# JacdacRp2040BrainEc30_124_snapshot_with_.net
KiCad netlist of a schematic drawn in Altium Designer
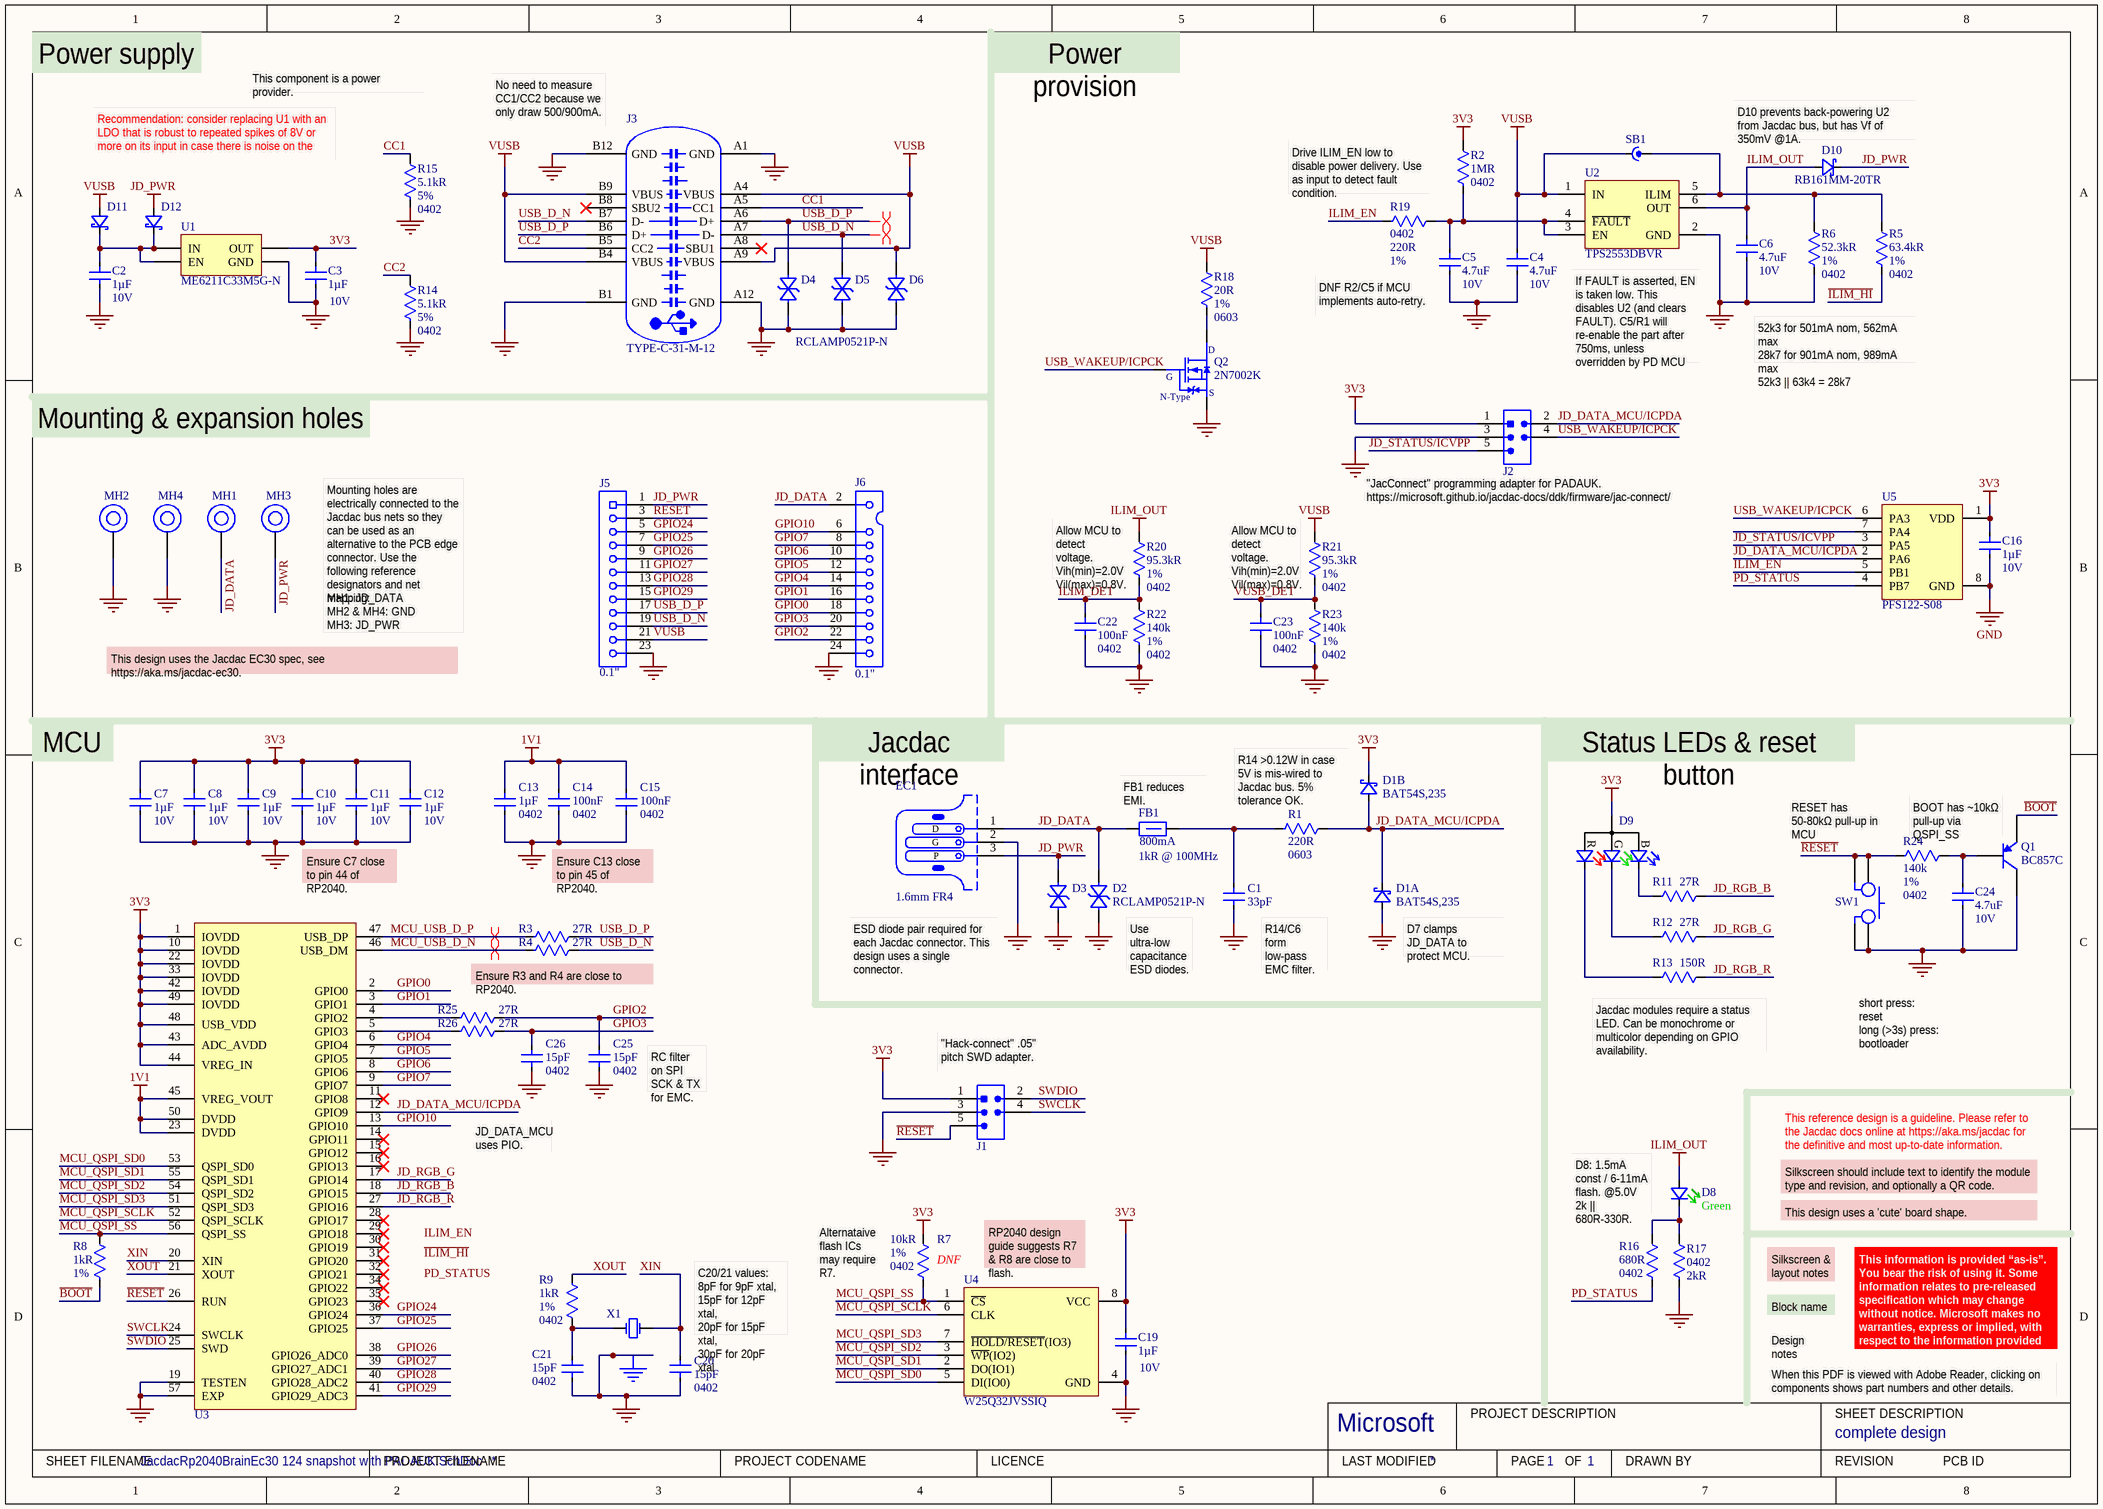
[diagram p0: JacdacRp2040BrainEc30 124 snapshot with PADAUK.SchDoc]

(export (version "E")
  (design (tool "Eeschema 10.0.6"))
  (components
    (comp (ref "C1")
      (value "CL05C330JB51PNC")
      (footprint "C0402_0.55MM - without outline")
      (description "CAP CER 33PF 50V NP0 0402")
      (fields
        (field (name "MANUFACTURER") "Samsung")
        (field (name "TOLERANCE") "5%")
        (field (name "CAPACITANCE") "33pF")
        (field (name "CHECKED") "?")
        (field (name "CREATED") "DG")
      )
      (libsource (lib "Samsung") (part "CL05C330JB51PNC"))
    )
    (comp (ref "C2")
      (value "CL05A105KP5NNNC")
      (footprint "C0402_0.55MM - without outline")
      (description "CAP CER 1UF 10V X5R 0402")
      (fields
        (field (name "MANUFACTURER") "Samsung")
        (field (name "TOLERANCE") "10%")
        (field (name "CAPACITANCE") "1µF")
        (field (name "VOLTAGE RATING") "10V")
        (field (name "CREATED") "DG")
        (field (name "CHECKED") "?")
      )
      (libsource (lib "Samsung") (part "CL05A105KP5NNNC"))
    )
    (comp (ref "C3")
      (value "CL05A105KP5NNNC")
      (footprint "C0402_0.55MM - without outline")
      (description "CAP CER 1UF 10V X5R 0402")
      (fields
        (field (name "MANUFACTURER") "Samsung")
        (field (name "TOLERANCE") "10%")
        (field (name "CAPACITANCE") "1µF")
        (field (name "VOLTAGE RATING") "10V")
        (field (name "CREATED") "DG")
        (field (name "CHECKED") "?")
      )
      (libsource (lib "Samsung") (part "CL05A105KP5NNNC"))
    )
    (comp (ref "C4")
      (value "CL05A475MP5NRNC")
      (footprint "SAMSUNG-CAP-0402:C0402_0.55mm - without outline")
      (description "CAP CER 4.7UF 10V X5R 0402")
      (fields
        (field (name "MANUFACTURER") "Samsung")
        (field (name "TOLERANCE") "20%")
        (field (name "CAPACITANCE") "4.7uF")
        (field (name "VOLTAGE RATING") "10V")
        (field (name "CREATED BY") "D. Gakure")
        (field (name "CHECKED BY") "?")
      )
      (libsource (lib "Samsung") (part "CL05A475MP5NRNC"))
    )
    (comp (ref "C5")
      (value "CL05A475MP5NRNC")
      (footprint "SAMSUNG-CAP-0402:C0402_0.55mm - without outline")
      (description "CAP CER 4.7UF 10V X5R 0402")
      (fields
        (field (name "MANUFACTURER") "Samsung")
        (field (name "TOLERANCE") "20%")
        (field (name "CAPACITANCE") "4.7uF")
        (field (name "VOLTAGE RATING") "10V")
        (field (name "CREATED BY") "D. Gakure")
        (field (name "CHECKED BY") "?")
      )
      (libsource (lib "Samsung") (part "CL05A475MP5NRNC"))
    )
    (comp (ref "C6")
      (value "CL05A475MP5NRNC")
      (footprint "SAMSUNG-CAP-0402:C0402_0.55mm - without outline")
      (description "CAP CER 4.7UF 10V X5R 0402")
      (fields
        (field (name "MANUFACTURER") "Samsung")
        (field (name "TOLERANCE") "20%")
        (field (name "CAPACITANCE") "4.7uF")
        (field (name "VOLTAGE RATING") "10V")
        (field (name "CREATED BY") "D. Gakure")
        (field (name "CHECKED BY") "?")
      )
      (libsource (lib "Samsung") (part "CL05A475MP5NRNC"))
    )
    (comp (ref "C7")
      (value "CL05A105KP5NNNC")
      (footprint "C0402_0.55MM - without outline")
      (description "CAP CER 1UF 10V X5R 0402")
      (fields
        (field (name "MANUFACTURER") "Samsung")
        (field (name "TOLERANCE") "10%")
        (field (name "CAPACITANCE") "1µF")
        (field (name "VOLTAGE RATING") "10V")
        (field (name "CREATED") "DG")
        (field (name "CHECKED") "?")
      )
      (libsource (lib "Samsung") (part "CL05A105KP5NNNC"))
    )
    (comp (ref "C8")
      (value "CL05A105KP5NNNC")
      (footprint "C0402_0.55MM - without outline")
      (description "CAP CER 1UF 10V X5R 0402")
      (fields
        (field (name "MANUFACTURER") "Samsung")
        (field (name "TOLERANCE") "10%")
        (field (name "CAPACITANCE") "1µF")
        (field (name "VOLTAGE RATING") "10V")
        (field (name "CREATED") "DG")
        (field (name "CHECKED") "?")
      )
      (libsource (lib "Samsung") (part "CL05A105KP5NNNC"))
    )
    (comp (ref "C9")
      (value "CL05A105KP5NNNC")
      (footprint "C0402_0.55MM - without outline")
      (description "CAP CER 1UF 10V X5R 0402")
      (fields
        (field (name "MANUFACTURER") "Samsung")
        (field (name "TOLERANCE") "10%")
        (field (name "CAPACITANCE") "1µF")
        (field (name "VOLTAGE RATING") "10V")
        (field (name "CREATED") "DG")
        (field (name "CHECKED") "?")
      )
      (libsource (lib "Samsung") (part "CL05A105KP5NNNC"))
    )
    (comp (ref "C10")
      (value "CL05A105KP5NNNC")
      (footprint "C0402_0.55MM - without outline")
      (description "CAP CER 1UF 10V X5R 0402")
      (fields
        (field (name "MANUFACTURER") "Samsung")
        (field (name "TOLERANCE") "10%")
        (field (name "CAPACITANCE") "1µF")
        (field (name "VOLTAGE RATING") "10V")
        (field (name "CREATED") "DG")
        (field (name "CHECKED") "?")
      )
      (libsource (lib "Samsung") (part "CL05A105KP5NNNC"))
    )
    (comp (ref "C11")
      (value "CL05A105KP5NNNC")
      (footprint "C0402_0.55MM - without outline")
      (description "CAP CER 1UF 10V X5R 0402")
      (fields
        (field (name "MANUFACTURER") "Samsung")
        (field (name "TOLERANCE") "10%")
        (field (name "CAPACITANCE") "1µF")
        (field (name "VOLTAGE RATING") "10V")
        (field (name "CREATED") "DG")
        (field (name "CHECKED") "?")
      )
      (libsource (lib "Samsung") (part "CL05A105KP5NNNC"))
    )
    (comp (ref "C12")
      (value "CL05A105KP5NNNC")
      (footprint "C0402_0.55MM - without outline")
      (description "CAP CER 1UF 10V X5R 0402")
      (fields
        (field (name "MANUFACTURER") "Samsung")
        (field (name "TOLERANCE") "10%")
        (field (name "CAPACITANCE") "1µF")
        (field (name "VOLTAGE RATING") "10V")
        (field (name "CREATED") "DG")
        (field (name "CHECKED") "?")
      )
      (libsource (lib "Samsung") (part "CL05A105KP5NNNC"))
    )
    (comp (ref "C13")
      (value "CL05A105KP5NNNC")
      (footprint "C0402_0.55MM - without outline")
      (description "CAP CER 1UF 10V X5R 0402")
      (fields
        (field (name "MANUFACTURER") "Samsung")
        (field (name "CASE/PACKAGE") "0402")
        (field (name "TOLERANCE") "10%")
        (field (name "CAPACITANCE") "1µF")
        (field (name "CREATED") "DG")
        (field (name "CHECKED") "?")
      )
      (libsource (lib "Samsung") (part "CL05A105KP5NNNC"))
    )
    (comp (ref "C14")
      (value "CL05B104KP5NNNC")
      (footprint "SAMSUNG-CAP-0402:C0402_0.55MM - without outline")
      (description "CAP CER 0.1UF 10V X7R 0402")
      (fields
        (field (name "MANUFACTURER") "Samsung")
        (field (name "TOLERANCE") "10%")
        (field (name "CAPACITANCE") "100nF")
        (field (name "CASE CODE (IMPERIAL)") "0402")
        (field (name "CREATED") "DG")
        (field (name "CHECKED") "?")
      )
      (libsource (lib "Samsung") (part "CL05B104KP5NNNC"))
    )
    (comp (ref "C15")
      (value "CL05B104KP5NNNC")
      (footprint "SAMSUNG-CAP-0402:C0402_0.55MM - without outline")
      (description "CAP CER 0.1UF 10V X7R 0402")
      (fields
        (field (name "MANUFACTURER") "Samsung")
        (field (name "TOLERANCE") "10%")
        (field (name "CAPACITANCE") "100nF")
        (field (name "CASE CODE (IMPERIAL)") "0402")
        (field (name "CREATED") "DG")
        (field (name "CHECKED") "?")
      )
      (libsource (lib "Samsung") (part "CL05B104KP5NNNC"))
    )
    (comp (ref "C16")
      (value "CL05A105KP5NNNC")
      (footprint "SAMSUNG-CAP-0402:C0402_0.55MM - without outline")
      (description "CAP CER 1UF 10V X5R 0402")
      (fields
        (field (name "MANUFACTURER") "Samsung")
        (field (name "TOLERANCE") "10%")
        (field (name "CAPACITANCE") "1µF")
        (field (name "VOLTAGE RATING") "10V")
        (field (name "CREATED") "DG")
        (field (name "CHECKED") "?")
      )
      (libsource (lib "Samsung") (part "CL05A105KP5NNNC"))
    )
    (comp (ref "C19")
      (value "CL05A105KP5NNNC")
      (footprint "C0402_0.55MM - without outline")
      (description "CAP CER 1UF 10V X5R 0402")
      (fields
        (field (name "MANUFACTURER") "Samsung")
        (field (name "TOLERANCE") "10%")
        (field (name "CAPACITANCE") "1µF")
        (field (name "VOLTAGE RATING") "10V")
        (field (name "CREATED") "DG")
        (field (name "CHECKED") "?")
      )
      (libsource (lib "Samsung") (part "CL05A105KP5NNNC"))
    )
    (comp (ref "C20")
      (value "CL05C150JB5NNNC")
      (footprint "C0402_0.55MM - without outline")
      (description "CAP CER 15PF 50V C0G/NP0 0402")
      (fields
        (field (name "MANUFACTURER") "Samsung")
        (field (name "TOLERANCE") "5%")
        (field (name "CAPACITANCE") "15pF")
        (field (name "CASE/PACKAGE") "0402")
      )
      (libsource (lib "Samsung") (part "CL05C150JB5NNNC"))
    )
    (comp (ref "C21")
      (value "CL05C150JB5NNNC")
      (footprint "C0402_0.55MM - without outline")
      (description "CAP CER 15PF 50V C0G/NP0 0402")
      (fields
        (field (name "MANUFACTURER") "Samsung")
        (field (name "TOLERANCE") "5%")
        (field (name "CAPACITANCE") "15pF")
        (field (name "CASE/PACKAGE") "0402")
      )
      (libsource (lib "Samsung") (part "CL05C150JB5NNNC"))
    )
    (comp (ref "C22")
      (value "CL05B104KP5NNNC")
      (footprint "SAMSUNG-CAP-0402:C0402_0.55MM - without outline")
      (description "CAP CER 0.1UF 10V X7R 0402")
      (fields
        (field (name "MANUFACTURER") "Samsung")
        (field (name "TOLERANCE") "10%")
        (field (name "CAPACITANCE") "100nF")
        (field (name "CASE CODE (IMPERIAL)") "0402")
        (field (name "CREATED") "DG")
        (field (name "CHECKED") "?")
      )
      (libsource (lib "Samsung") (part "CL05B104KP5NNNC"))
    )
    (comp (ref "C23")
      (value "CL05B104KP5NNNC")
      (footprint "SAMSUNG-CAP-0402:C0402_0.55MM - without outline")
      (description "CAP CER 0.1UF 10V X7R 0402")
      (fields
        (field (name "MANUFACTURER") "Samsung")
        (field (name "TOLERANCE") "10%")
        (field (name "CAPACITANCE") "100nF")
        (field (name "CASE CODE (IMPERIAL)") "0402")
        (field (name "CREATED") "DG")
        (field (name "CHECKED") "?")
      )
      (libsource (lib "Samsung") (part "CL05B104KP5NNNC"))
    )
    (comp (ref "C24")
      (value "CL05A475MP5NRNC")
      (footprint "SAMSUNG-CAP-0402:C0402_0.55mm - without outline")
      (description "CAP CER 4.7UF 10V X5R 0402")
      (fields
        (field (name "MANUFACTURER") "Samsung")
        (field (name "TOLERANCE") "20%")
        (field (name "CAPACITANCE") "4.7uF")
        (field (name "VOLTAGE RATING") "10V")
        (field (name "CREATED BY") "D. Gakure")
        (field (name "CHECKED BY") "?")
      )
      (libsource (lib "Samsung") (part "CL05A475MP5NRNC"))
    )
    (comp (ref "C25")
      (value "CL05C150JB5NNNC")
      (footprint "SAMSUNG-CAP-0402:C0402_0.55MM - without outline")
      (description "CAP CER 15PF 50V C0G/NP0 0402")
      (fields
        (field (name "MANUFACTURER") "Samsung")
        (field (name "TOLERANCE") "5%")
        (field (name "CAPACITANCE") "15pF")
        (field (name "CASE/PACKAGE") "0402")
      )
      (libsource (lib "Samsung") (part "CL05C150JB5NNNC"))
    )
    (comp (ref "C26")
      (value "CL05C150JB5NNNC")
      (footprint "SAMSUNG-CAP-0402:C0402_0.55MM - without outline")
      (description "CAP CER 15PF 50V C0G/NP0 0402")
      (fields
        (field (name "MANUFACTURER") "Samsung")
        (field (name "TOLERANCE") "5%")
        (field (name "CAPACITANCE") "15pF")
        (field (name "CASE/PACKAGE") "0402")
      )
      (libsource (lib "Samsung") (part "CL05C150JB5NNNC"))
    )
    (comp (ref "D1")
      (value "BAT54S")
      (footprint "NXP-BAT54S-TO-236AB - without outline")
      (description "DIODE ARRAY SCHOTTKY 30V SOT23")
      (fields (field (name "MANUFACTURER") "Nexperia") (field (name "MANUFACTURER PART NUMBER") "BAT54S,235"))
      (libsource (lib "NXP") (part "BAT54S"))
    )
    (comp (ref "D2")
      (value "RCLAMP0521P-N")
      (footprint "TVS 0402 - L")
      (description "Bidirectional 5V (Max) 6V 16V 3.5A (8/20us) 0402 TVS RoHS")
      (fields
        (field (name "MANUFACTURER") "Born Semiconductor")
        (field (name "MANUFACTURER PART NUMBER") "RCLAMP0521P-N")
        (field (name "CREATED BY") "D Gakure")
        (field (name "CHECKED BY") "?")
      )
      (libsource (lib "BornSemiconductor") (part "RCLAMP0521P-N"))
    )
    (comp (ref "D3")
      (value "RCLAMP0521P-N")
      (footprint "TVS 0402 - L")
      (description "Bidirectional 5V (Max) 6V 16V 3.5A (8/20us) 0402 TVS RoHS")
      (fields
        (field (name "MANUFACTURER") "Born Semiconductor")
        (field (name "CREATED BY") "D Gakure")
        (field (name "CHECKED BY") "?")
      )
      (libsource (lib "BornSemiconductor") (part "RCLAMP0521P-N"))
    )
    (comp (ref "D4")
      (value "RCLAMP0521P-N")
      (footprint "TVS 0402 - L")
      (description "Bidirectional 5V (Max) 6V 16V 3.5A (8/20us) 0402 TVS RoHS")
      (fields
        (field (name "MANUFACTURER") "Born Semiconductor")
        (field (name "CREATED BY") "D Gakure")
        (field (name "CHECKED BY") "?")
      )
      (libsource (lib "BornSemiconductor") (part "RCLAMP0521P-N"))
    )
    (comp (ref "D5")
      (value "RCLAMP0521P-N")
      (footprint "TVS 0402 - L")
      (description "Bidirectional 5V (Max) 6V 16V 3.5A (8/20us) 0402 TVS RoHS")
      (fields
        (field (name "MANUFACTURER") "Born Semiconductor")
        (field (name "CREATED BY") "D Gakure")
        (field (name "CHECKED BY") "?")
      )
      (libsource (lib "BornSemiconductor") (part "RCLAMP0521P-N"))
    )
    (comp (ref "D6")
      (value "RCLAMP0521P-N")
      (footprint "TVS 0402 - L")
      (description "Bidirectional 5V (Max) 6V 16V 3.5A (8/20us) 0402 TVS RoHS")
      (fields
        (field (name "MANUFACTURER") "Born Semiconductor")
        (field (name "MANUFACTURER PART NUMBER") "RCLAMP0521P-N")
        (field (name "CREATED BY") "D Gakure")
        (field (name "CHECKED BY") "?")
      )
      (libsource (lib "BornSemiconductor") (part "RCLAMP0521P-N"))
    )
    (comp (ref "D8")
      (value "~")
      (footprint "Green_0603:0603 Green")
      (description "LED GREEN DIFFUSED 0603 SMD")
      (fields
        (field (name "MANUFACTURER") "Everlight Elec")
        (field (name "MANUFACTURER PART NUMBER") "19-217/GHC-YR1S2/3T")
        (field (name "COLOUR") "Green")
      )
      (libsource (lib "EverlightElec") (part "19-217/GHC-YR1S2/3T"))
    )
    (comp (ref "D9")
      (value "TZ-P4-1615RGBTCA1-0.55T")
      (footprint "TZ-P4-1615RGBTCA1-0.55T")
      (description "1615 Light Emitting Diodes (LED) RoHS")
      (fields
        (field (name "MANUFACTURER") "TUOZHAN")
        (field (name "CREATED BY") "D. Gakure")
        (field (name "CHECKED BY") "?")
      )
      (libsource (lib "Tuozhan") (part "TZ-P4-1615RGBTCA1-0.55T"))
    )
    (comp (ref "D10")
      (value "RB161MM-20TR")
      (footprint "SOD-123F:SOD-123F - without outline")
      (description "ROHM - RB161MM-20TR - Schottky-Gleichrichterdiode, 20 V, 1 A, Einfach, SOD-123FL, 2 Pin(s), 350 mV")
      (fields (field (name "MANUFACTURER") "Rohm") (field (name "MANUFACTURER PART NUMBER") "RB161MM-20TR"))
      (libsource (lib "Rohm") (part "RB161MM-20TR"))
    )
    (comp (ref "D11")
      (value "RB161MM-20TR")
      (footprint "SOD-123F:SOD-123F - without outline")
      (description "ROHM - RB161MM-20TR - Schottky-Gleichrichterdiode, 20 V, 1 A, Einfach, SOD-123FL, 2 Pin(s), 350 mV")
      (fields (field (name "MANUFACTURER") "Rohm"))
      (libsource (lib "Rohm") (part "RB161MM-20TR"))
    )
    (comp (ref "D12")
      (value "RB161MM-20TR")
      (footprint "SOD-123F:SOD-123F - without outline")
      (description "ROHM - RB161MM-20TR - Schottky-Gleichrichterdiode, 20 V, 1 A, Einfach, SOD-123FL, 2 Pin(s), 350 mV")
      (fields (field (name "MANUFACTURER") "Rohm"))
      (libsource (lib "Rohm") (part "RB161MM-20TR"))
    )
    (comp (ref "EC1")
      (value "3 pin JACDAC edge connector")
      (footprint "JACDAC_edge_connector:JACDAC_EDGE_CONNECTOR_NO_TRACES")
      (description "3 pin Jacdac edge connector 1.27mm pitch")
      (fields
        (field (name "MANUFACTURER PART NUMBER") "JACDAC_EDGE_CONNECTOR")
        (field (name "PCB TYPE") "1.6mm FR4")
        (field (name "CHECKED BY") "?")
        (field (name "CREATED BY") "D. Gakure")
      )
      (libsource (lib "generic-con") (part "Jacdac edge connector"))
    )
    (comp (ref "FB1")
      (value "TDK MPZ1608S102ATA00")
      (footprint "TDK MPZ1608 0.8mm - without outline")
      (description "0603 1k@100MHz 0.8A chip")
      (fields
        (field (name "TOLERANCE") "25%")
        (field (name "MANUFACTURER") "TDK")
        (field (name "CURRENT RATING") "800mA")
        (field (name "IMPEDANCE") "1kR @ 100MHz")
      )
      (libsource (lib "TDK") (part "TDK MPZ1608S102ATA00"))
    )
    (comp (ref "J1")
      (value "Hack Connect Mini 1.27 mm pitch 2-row")
      (footprint "HACK_CONNECT_MINI_5_X_1_27")
      (libsource (lib "generic-con") (part "HACK_CONNECT_MINI"))
    )
    (comp (ref "J2")
      (value "Hack Connect Mini 1.27 mm pitch 2-row")
      (footprint "HackConnect:HACK_CONNECT_MINI_5_X_1_27_0.559mm_TH")
      (libsource (lib "generic-con") (part "HACK_CONNECT_MINI"))
    )
    (comp (ref "J3")
      (value "TYPE-C-31-M-12")
      (footprint "TYPE-C-31-M-12")
      (description "USB - Type C Female 16 USB Connectors RoHS")
      (fields
        (field (name "MANUFACTURER") "Korean Hroparts Elec")
        (field (name "MANUFACTURER PART NUMBER") "TYPE-C-31-M-12")
      )
      (libsource (lib "KoreanHropartsElec") (part "TYPE-C-31-M-12"))
    )
    (comp (ref "J5")
      (value "0.1\"")
      (footprint "generic-con-0.1inch:Jacdac EC30 stamp holes 30mm bottom")
      (description "2.54mm, 12x1 way, vertical, TH")
      (fields (field (name "MANUFACTURER") "Generic") (field (name "MANUFACTURER PART NUMBER") "TBD"))
      (libsource (lib "generic-con") (part "Jacdac EC30 stamp holes 30mm bottom"))
    )
    (comp (ref "J6")
      (value "0.1\"")
      (footprint "generic-con-0.1inch:Jacdac EC30 stamp holes 30mm top")
      (description "2.54mm, 12x1 way, vertical, TH")
      (fields (field (name "MANUFACTURER") "Generic") (field (name "MANUFACTURER PART NUMBER") "TBD"))
      (libsource (lib "generic-con") (part "Jacdac EC30 stamp holes 30mm top"))
    )
    (comp (ref "MH1")
      (value "MH_7.0MMK_4.4MMC_3.1MMD_PTH")
      (footprint "MH_7.0MMK_4.4MMC_3.1MMD_PTH:MH_7.0MMK_4.4MMC_3.1MMD_PTH")
      (description "Mounting Hole 7.0mm keepout, 4.4mm annualar ring and 3.1mm Drill PTH")
      (libsource (lib "generic") (part "MH_7.0MMK_4.4MMC_3.1MMD_PTH"))
    )
    (comp (ref "MH2")
      (value "MH_7.0MMK_4.4MMC_3.1MMD_PTH")
      (footprint "MH_7.0MMK_4.4MMC_3.1MMD_PTH:MH_7.0MMK_4.4MMC_3.1MMD_PTH")
      (description "Mounting Hole 7.0mm keepout, 4.4mm annualar ring and 3.1mm Drill PTH")
      (libsource (lib "generic") (part "MH_7.0MMK_4.4MMC_3.1MMD_PTH"))
    )
    (comp (ref "MH3")
      (value "MH_7.0MMK_4.4MMC_3.1MMD_PTH")
      (footprint "MH_7.0MMK_4.4MMC_3.1MMD_PTH:MH_7.0MMK_4.4MMC_3.1MMD_PTH")
      (description "Mounting Hole 7.0mm keepout, 4.4mm annualar ring and 3.1mm Drill PTH")
      (libsource (lib "generic") (part "MH_7.0MMK_4.4MMC_3.1MMD_PTH"))
    )
    (comp (ref "MH4")
      (value "MH_7.0MMK_4.4MMC_3.1MMD_PTH")
      (footprint "MH_7.0MMK_4.4MMC_3.1MMD_PTH:MH_7.0MMK_4.4MMC_3.1MMD_PTH")
      (description "Mounting Hole 7.0mm keepout, 4.4mm annualar ring and 3.1mm Drill PTH")
      (libsource (lib "generic") (part "MH_7.0MMK_4.4MMC_3.1MMD_PTH"))
    )
    (comp (ref "Q1")
      (value "BC857C")
      (footprint "NXP-SOT23:NXP-SOT23 - without outline")
      (description "PNP Ic=-100mA Vceo=-45V hfe=420~800 P=250mW")
      (libsource (lib "NXP") (part "BC857C,215-whitesch"))
    )
    (comp (ref "Q2")
      (value "2N7002K")
      (footprint "ON_SEMI-SOT23:SOT23-ONS")
      (description "MOSFET Transistor, N Channel, 300 mA, 60 V, 2 ohm, 10 V, 2.5 V")
      (fields
        (field (name "MANUFACTURER") "ON Semiconductor / Fairchild")
        (field (name "MANUFACTURER PART NUMBER") "2N7002K")
        (field (name "VOLTAGE") "60V")
        (field (name "CHECKED BY") "?")
        (field (name "CREATED BY") "D. Gakure")
      )
      (libsource (lib "OnSemiconductor") (part "2N7002K"))
    )
    (comp (ref "R1")
      (value "220R")
      (footprint "YAGEO-0603:RC0603")
      (description "Res Thick Film 0603 220 Ohm 1% 0.1W(1/10W) ±100ppm/°C Pad SMD T/R")
      (fields
        (field (name "MANUFACTURER") "Yageo")
        (field (name "MANUFACTURER PART NUMBER") "RC0603FR-07220RL")
        (field (name "RESISTANCE") "220R")
        (field (name "CASE/PACKAGE") "0603")
      )
      (libsource (lib "Yageo") (part "RC0603FR-07220RL"))
    )
    (comp (ref "R2")
      (value "~")
      (footprint "YAGEO-0402:R0402 - Without outline")
      (description "RES SMD 1M OHM 1% 1/16W 0402")
      (fields
        (field (name "MANUFACTURER") "Yageo")
        (field (name "MANUFACTURER PART NUMBER") "RC0402FR-071ML")
        (field (name "RESISTANCE") "1MR")
        (field (name "CASE CODE (IMPERIAL)") "0402")
        (field (name "CREATED BY") "D. Gakure")
        (field (name "CHECKED BY") "?")
      )
      (libsource (lib "Yageo") (part "RC0402FR-071ML"))
    )
    (comp (ref "R3")
      (value "RC0402FR-0727RL")
      (footprint "R0402 - Without outline")
      (description "RES SMD 27 OHM 1% 1/16W 0402")
      (fields
        (field (name "MANUFACTURER") "Yageo")
        (field (name "TOLERANCE") "1%")
        (field (name "RESISTANCE") "27R")
      )
      (libsource (lib "Yageo") (part "RC0402FR-0727RL"))
    )
    (comp (ref "R4")
      (value "RC0402FR-0727RL")
      (footprint "R0402 - Without outline")
      (description "RES SMD 27 OHM 1% 1/16W 0402")
      (fields
        (field (name "MANUFACTURER") "Yageo")
        (field (name "TOLERANCE") "1%")
        (field (name "RESISTANCE") "27R")
      )
      (libsource (lib "Yageo") (part "RC0402FR-0727RL"))
    )
    (comp (ref "R5")
      (value "RC0402FR-0763K4L")
      (footprint "YAGEO-0402:R0402 - Without outline")
      (description "RES SMD 63.4K OHM 1% 1/16W 0402")
      (fields
        (field (name "MANUFACTURER") "Yageo")
        (field (name "RESISTANCE") "63.4kR")
        (field (name "TOLERANCE") "1%")
        (field (name "CASE CODE (IMPERIAL)") "0402")
        (field (name "CREATED BY") "D. Gakure")
        (field (name "CHECKED BY") "?")
      )
      (libsource (lib "Yageo") (part "RC0402FR-0763K4L"))
    )
    (comp (ref "R6")
      (value "RC0402FR-0752K3L")
      (footprint "R0402 - Without outline")
      (description "RES SMD 52.3K OHM 1% 1/16W 0402")
      (fields
        (field (name "MANUFACTURER") "Yageo")
        (field (name "RESISTANCE") "52.3kR")
        (field (name "TOLERANCE") "1%")
        (field (name "CASE CODE (IMPERIAL)") "0402")
        (field (name "CREATED BY") "D. Gakure")
        (field (name "CHECKED BY") "?")
      )
      (libsource (lib "Yageo") (part "RC0402FR-0752K3L"))
    )
    (comp (ref "R7")
      (value "10k")
      (footprint "R0402 - Without outline")
      (description "RES SMD 10K OHM 1% 1/16W 0402")
      (fields
        (field (name "MANUFACTURER") "Yageo")
        (field (name "MANUFACTURER PART NUMBER") "RC0402FR-0710KL")
        (field (name "RESISTANCE") "10kR")
        (field (name "TOLERANCE") "1%")
        (field (name "CASE CODE (IMPERIAL)") "0402")
        (field (name "CHECKED") "?")
        (field (name "CREATED") "DG")
      )
      (libsource (lib "Yageo") (part "RC0402FR-0710KL"))
    )
    (comp (ref "R8")
      (value "RC0402FR-071KL")
      (footprint "R0402 - Without outline")
      (description "RES SMD 1K OHM 1% 1/16W 0402")
      (fields
        (field (name "MANUFACTURER") "Yageo")
        (field (name "RESISTANCE") "1kR")
        (field (name "TOLERANCE") "1%")
        (field (name "CREATED") "D.G")
        (field (name "CHECKED") "?")
      )
      (libsource (lib "Yageo") (part "RC0402FR-071KL"))
    )
    (comp (ref "R9")
      (value "RC0402FR-071KL")
      (footprint "R0402 - Without outline")
      (description "RES SMD 1K OHM 1% 1/16W 0402")
      (fields
        (field (name "MANUFACTURER") "Yageo")
        (field (name "RESISTANCE") "1kR")
        (field (name "TOLERANCE") "1%")
        (field (name "CASE CODE (IMPERIAL)") "0402")
        (field (name "CREATED") "D.G")
        (field (name "CHECKED") "?")
      )
      (libsource (lib "Yageo") (part "RC0402FR-071KL"))
    )
    (comp (ref "R11")
      (value "RC0402FR-0727RL")
      (footprint "R0402 - Without outline")
      (description "RES SMD 27 OHM 1% 1/16W 0402")
      (fields
        (field (name "MANUFACTURER") "Yageo")
        (field (name "TOLERANCE") "1%")
        (field (name "RESISTANCE") "27R")
      )
      (libsource (lib "Yageo") (part "RC0402FR-0727RL"))
    )
    (comp (ref "R12")
      (value "RC0402FR-0727RL")
      (footprint "R0402 - Without outline")
      (description "RES SMD 27 OHM 1% 1/16W 0402")
      (fields
        (field (name "MANUFACTURER") "Yageo")
        (field (name "TOLERANCE") "1%")
        (field (name "RESISTANCE") "27R")
      )
      (libsource (lib "Yageo") (part "RC0402FR-0727RL"))
    )
    (comp (ref "R13")
      (value "RC0402FR-07150RL")
      (footprint "R0402 - Without outline")
      (description "RES SMD 150 OHM 1% 1/16W 0402")
      (fields
        (field (name "MANUFACTURER") "Yageo")
        (field (name "RESISTANCE") "150R")
        (field (name "TOLERANCE") "1%")
        (field (name "CREATED BY") "D. Gakure")
        (field (name "CHECKED BY") "?")
      )
      (libsource (lib "Yageo") (part "RC0402FR-07150RL"))
    )
    (comp (ref "R14")
      (value "RC0402JR-075K1L")
      (footprint "R0402 - Without outline")
      (description "RES SMD 5.1K OHM 5% 1/16W 0402")
      (fields
        (field (name "MANUFACTURER") "Yageo")
        (field (name "RESISTANCE") "5.1kR")
        (field (name "TOLERANCE") "5%")
        (field (name "CASE CODE (IMPERIAL)") "0402")
        (field (name "CREATED BY") "D. Gakure")
        (field (name "CHECKED BY") "?")
      )
      (libsource (lib "Yageo") (part "RC0402JR-075K1L"))
    )
    (comp (ref "R15")
      (value "RC0402JR-075K1L")
      (footprint "R0402 - Without outline")
      (description "RES SMD 5.1K OHM 5% 1/16W 0402")
      (fields
        (field (name "MANUFACTURER") "Yageo")
        (field (name "RESISTANCE") "5.1kR")
        (field (name "TOLERANCE") "5%")
        (field (name "CASE CODE (IMPERIAL)") "0402")
        (field (name "CREATED BY") "D. Gakure")
        (field (name "CHECKED BY") "?")
      )
      (libsource (lib "Yageo") (part "RC0402JR-075K1L"))
    )
    (comp (ref "R16")
      (value "RC0402FR-07680RL")
      (footprint "YAGEO-0402:R0402 - Without outline")
      (description "RES SMD 680 OHM 1% 1/16W 0402")
      (fields
        (field (name "MANUFACTURER") "Yageo")
        (field (name "RESISTANCE") "680R")
        (field (name "TOLERANCE") "1%")
        (field (name "CASE CODE (IMPERIAL)") "0402")
        (field (name "CREATED BY") "D. Gakure")
      )
      (libsource (lib "Yageo") (part "RC0402FR-07680RL"))
    )
    (comp (ref "R17")
      (value "RC0402FR-072KL")
      (footprint "YAGEO-0402:R0402 - Without outline")
      (description "RES SMD 2K OHM 1% 1/16W 0402")
      (fields
        (field (name "MANUFACTURER") "Yageo")
        (field (name "CASE/PACKAGE") "0402")
        (field (name "TOLERANCE") "1%")
        (field (name "RESISTANCE") "2kR")
        (field (name "CREATED BY") "D. Gakure")
      )
      (libsource (lib "Yageo") (part "RC0402FR-072KL"))
    )
    (comp (ref "R18")
      (value "RC0603FR-0720RL")
      (footprint "YAGEO-0603:RC0603")
      (description "RES SMD 20 OHM 1% 1/10W 0603")
      (fields
        (field (name "MANUFACTURER") "Yageo")
        (field (name "RESISTANCE") "20R")
        (field (name "TOLERANCE") "1%")
        (field (name "CASE CODE (IMPERIAL)") "0603")
        (field (name "CREATED BY") "D. Gakure")
      )
      (libsource (lib "Yageo") (part "RC0603FR-0720RL"))
    )
    (comp (ref "R19")
      (value "RC0402FR-07220RL")
      (footprint "YAGEO-0402:R0402 - without outline")
      (description "RES SMD 220 OHM 1% 1/16W 0402")
      (fields
        (field (name "MANUFACTURER") "Yageo")
        (field (name "CASE CODE (IMPERIAL)") "0402")
        (field (name "RESISTANCE") "220R")
        (field (name "TOLERANCE") "1%")
        (field (name "CREATED") "D.G")
        (field (name "CHECKED") "?")
      )
      (libsource (lib "Yageo") (part "RC0402FR-07220RL"))
    )
    (comp (ref "R20")
      (value "RC0402FR-0795K3L")
      (footprint "YAGEO-0402:R0402 - Without outline")
      (description "RES SMD 95.3K OHM 1% 1/16W 0402")
      (fields
        (field (name "MANUFACTURER") "Yageo")
        (field (name "RESISTANCE") "95.3kR")
        (field (name "TOLERANCE") "1%")
        (field (name "CASE CODE (IMPERIAL)") "0402")
        (field (name "CREATED BY") "D. Gakure")
      )
      (libsource (lib "Yageo") (part "RC0402FR-0795K3L"))
    )
    (comp (ref "R21")
      (value "RC0402FR-0795K3L")
      (footprint "YAGEO-0402:R0402 - Without outline")
      (description "RES SMD 95.3K OHM 1% 1/16W 0402")
      (fields
        (field (name "MANUFACTURER") "Yageo")
        (field (name "RESISTANCE") "95.3kR")
        (field (name "TOLERANCE") "1%")
        (field (name "CASE CODE (IMPERIAL)") "0402")
        (field (name "CREATED BY") "D. Gakure")
      )
      (libsource (lib "Yageo") (part "RC0402FR-0795K3L"))
    )
    (comp (ref "R22")
      (value "RC0402FR-07100KL")
      (footprint "YAGEO-0402:R0402 - Without outline")
      (description "RES SMD 140K OHM 1% 1/16W 0402")
      (fields
        (field (name "MANUFACTURER") "Yageo")
        (field (name "RESISTANCE") "140k")
        (field (name "TOLERANCE") "1%")
        (field (name "CASE/PACKAGE") "0402")
        (field (name "CREATED BY") "DG")
        (field (name "CHECKED BY") "?")
      )
      (libsource (lib "Yageo") (part "RC0402FR-07140KL"))
    )
    (comp (ref "R23")
      (value "RC0402FR-07100KL")
      (footprint "YAGEO-0402:R0402 - Without outline")
      (description "RES SMD 140K OHM 1% 1/16W 0402")
      (fields
        (field (name "MANUFACTURER") "Yageo")
        (field (name "RESISTANCE") "140k")
        (field (name "TOLERANCE") "1%")
        (field (name "CASE/PACKAGE") "0402")
        (field (name "CREATED BY") "DG")
        (field (name "CHECKED BY") "?")
      )
      (libsource (lib "Yageo") (part "RC0402FR-07140KL"))
    )
    (comp (ref "R24")
      (value "RC0402FR-07100KL")
      (footprint "YAGEO-0402:R0402 - Without outline")
      (description "RES SMD 140K OHM 1% 1/16W 0402")
      (fields
        (field (name "MANUFACTURER") "Yageo")
        (field (name "RESISTANCE") "140k")
        (field (name "TOLERANCE") "1%")
        (field (name "CASE/PACKAGE") "0402")
        (field (name "CREATED BY") "DG")
        (field (name "CHECKED BY") "?")
      )
      (libsource (lib "Yageo") (part "RC0402FR-07140KL"))
    )
    (comp (ref "R25")
      (value "RC0402FR-0727RL")
      (footprint "YAGEO-0402:R0402 - Without outline")
      (description "RES SMD 27 OHM 1% 1/16W 0402")
      (fields
        (field (name "MANUFACTURER") "Yageo")
        (field (name "TOLERANCE") "1%")
        (field (name "RESISTANCE") "27R")
      )
      (libsource (lib "Yageo") (part "RC0402FR-0727RL"))
    )
    (comp (ref "R26")
      (value "RC0402FR-0727RL")
      (footprint "YAGEO-0402:R0402 - Without outline")
      (description "RES SMD 27 OHM 1% 1/16W 0402")
      (fields
        (field (name "MANUFACTURER") "Yageo")
        (field (name "TOLERANCE") "1%")
        (field (name "RESISTANCE") "27R")
      )
      (libsource (lib "Yageo") (part "RC0402FR-0727RL"))
    )
    (comp (ref "SB1")
      (value "OpenSolderBlob")
      (footprint "SolderBlobA:SolderBlobB")
      (description "Open solder blob")
      (libsource (lib "generic") (part "OpenSolderBlob"))
    )
    (comp (ref "SW1")
      (value "UK-B0267-SP25Y")
      (footprint "USAKRO-UK-B0267-SP25Y")
      (description "SWITCH TACTILE SSPST 50mA @ 12VDC")
      (fields (field (name "MANUFACTURER") "USAKRO"))
      (libsource (lib "Usakro") (part "UK-B0267-SP25Y"))
    )
    (comp (ref "U1")
      (value "ME6211C33M5G-N")
      (footprint "MICRONE-SOT23-5")
      (description "6V 260mV @ 200mA(typ) - - Fixed 3.3V SOT-23-5 Linear Voltage Regulators (LDO) ROHS")
      (fields
        (field (name "MANUFACTURER") "MICRONE(Nanjing Micro One Elec)")
        (field (name "MANUFACTURER PART NUMBER") "ME6211C33M5G-N")
        (field (name "CREATED") "DG")
        (field (name "CHECKED") "?")
      )
      (libsource (lib "MICRONE(NanjingMicroOneElec)") (part "ME6211C33M5G-N"))
    )
    (comp (ref "U2")
      (value "TPS2553DBVR")
      (footprint "TI-TPS2553 - without_outline")
      (description "IC PWR SWITCH N-CHAN 1:1 SOT23-6")
      (fields
        (field (name "MANUFACTURER") "Texas Instruments")
        (field (name "MANUFACTURER PART NUMBER") "TPS2553DBVR")
      )
      (libsource (lib "TexasInstruments") (part "TPS2553DBVR"))
    )
    (comp (ref "U3")
      (value "RP2040")
      (footprint "RP2040:RP2040-SAFER-VIAS")
      (description "QFN-56_7x7 MCU")
      (fields (field (name "MANUFACTURER") "Raspberry Pi"))
      (libsource (lib "RaspberryPi") (part "RP2040"))
    )
    (comp (ref "U4")
      (value "~")
      (footprint "8-SOIC")
      (description "FLASH - NOR Memory IC 32Mb (4M x 8) SPI - Quad I/O 133 MHz 8-SOIC")
      (fields
        (field (name "MANUFACTURER") "Winbond")
        (field (name "MANUFACTURER PART NUMBER") "W25Q32JVSSIQ")
      )
      (libsource (lib "WinbondElectronics") (part "W25Q32JVSSIQ"))
    )
    (comp (ref "U5")
      (value "PFS122-S08")
      (footprint "PADAUK-SOP-8:SOP-8")
      (description "8bit MTP MCU with 12-bit ADC")
      (fields (field (name "MANUFACTURER") "PADAUK") (field (name "MANUFACTURER PART NUMBER") "PFS122-S08"))
      (libsource (lib "PADAUK") (part "PFS122-SO8"))
    )
    (comp (ref "X1")
      (value "generic SMD xtal 3.2x2.5mm")
      (footprint "generic-crystal:generic xtal 3.2x2.5")
      (description "Generic SMD xtal 3.2x2.5mm")
      (libsource (lib "generic-crystal") (part "generic SMD xtal 3.2x2.5mm"))
    )
  )
  (nets
    (net (code "1") (name "/CC1") (class "Default")
      (node (ref "J3") (pin "A5") (pinfunction "CC1_A5") (pintype "passive"))
      (node (ref "R15") (pin "1") (pinfunction "1_1") (pintype "passive"))
    )
    (net (code "2") (name "/CC2") (class "Default")
      (node (ref "J3") (pin "B5") (pinfunction "CC2_B5") (pintype "passive"))
      (node (ref "R14") (pin "1") (pinfunction "1_1") (pintype "passive"))
    )
    (net (code "3") (name "/GPIO0") (class "Default")
      (node (ref "J6") (pin "18") (pinfunction "17_18") (pintype "passive"))
      (node (ref "U3") (pin "2") (pinfunction "GPIO0_2") (pintype "passive"))
    )
    (net (code "4") (name "/GPIO1") (class "Default")
      (node (ref "J6") (pin "16") (pinfunction "15_16") (pintype "passive"))
      (node (ref "U3") (pin "3") (pinfunction "GPIO1_3") (pintype "passive"))
    )
    (net (code "5") (name "/GPIO2") (class "Default")
      (node (ref "C25") (pin "1") (pinfunction "1_1") (pintype "passive"))
      (node (ref "J6") (pin "22") (pinfunction "21_22") (pintype "passive"))
      (node (ref "R25") (pin "2") (pinfunction "2_2") (pintype "passive"))
    )
    (net (code "6") (name "/GPIO3") (class "Default")
      (node (ref "C26") (pin "1") (pinfunction "1_1") (pintype "passive"))
      (node (ref "J6") (pin "20") (pinfunction "19_20") (pintype "passive"))
      (node (ref "R26") (pin "2") (pinfunction "2_2") (pintype "passive"))
    )
    (net (code "7") (name "/GPIO4") (class "Default")
      (node (ref "J6") (pin "14") (pinfunction "13_14") (pintype "passive"))
      (node (ref "U3") (pin "6") (pinfunction "GPIO4_6") (pintype "passive"))
    )
    (net (code "8") (name "/GPIO5") (class "Default")
      (node (ref "J6") (pin "12") (pinfunction "11_12") (pintype "passive"))
      (node (ref "U3") (pin "7") (pinfunction "GPIO5_7") (pintype "passive"))
    )
    (net (code "9") (name "/GPIO6") (class "Default")
      (node (ref "J6") (pin "10") (pinfunction "9_10") (pintype "passive"))
      (node (ref "U3") (pin "8") (pinfunction "GPIO6_8") (pintype "passive"))
    )
    (net (code "10") (name "/GPIO7") (class "Default")
      (node (ref "J6") (pin "8") (pinfunction "7_8") (pintype "passive"))
      (node (ref "U3") (pin "9") (pinfunction "GPIO7_9") (pintype "passive"))
    )
    (net (code "11") (name "/GPIO10") (class "Default")
      (node (ref "J6") (pin "6") (pinfunction "5_6") (pintype "passive"))
      (node (ref "U3") (pin "13") (pinfunction "GPIO10_13") (pintype "passive"))
    )
    (net (code "12") (name "/GPIO24") (class "Default")
      (node (ref "J5") (pin "5") (pinfunction "5_5") (pintype "passive"))
      (node (ref "U3") (pin "36") (pinfunction "GPIO24_36") (pintype "passive"))
    )
    (net (code "13") (name "/GPIO25") (class "Default")
      (node (ref "J5") (pin "7") (pinfunction "7_7") (pintype "passive"))
      (node (ref "U3") (pin "37") (pinfunction "GPIO25_37") (pintype "passive"))
    )
    (net (code "14") (name "/GPIO26") (class "Default")
      (node (ref "J5") (pin "9") (pinfunction "9_9") (pintype "passive"))
      (node (ref "U3") (pin "38") (pinfunction "GPIO26_ADC0_38") (pintype "passive"))
    )
    (net (code "15") (name "/GPIO27") (class "Default")
      (node (ref "J5") (pin "11") (pinfunction "11_11") (pintype "passive"))
      (node (ref "U3") (pin "39") (pinfunction "GPIO27_ADC1_39") (pintype "passive"))
    )
    (net (code "16") (name "/GPIO28") (class "Default")
      (node (ref "J5") (pin "13") (pinfunction "13_13") (pintype "passive"))
      (node (ref "U3") (pin "40") (pinfunction "GPIO28_ADC2_40") (pintype "passive"))
    )
    (net (code "17") (name "/GPIO29") (class "Default")
      (node (ref "J5") (pin "15") (pinfunction "15_15") (pintype "passive"))
      (node (ref "U3") (pin "41") (pinfunction "GPIO29_ADC3_41") (pintype "passive"))
    )
    (net (code "18") (name "/ILIM_DET") (class "Default")
      (node (ref "C22") (pin "2") (pinfunction "2_2") (pintype "passive"))
      (node (ref "R20") (pin "1") (pinfunction "1_1") (pintype "passive"))
      (node (ref "R22") (pin "2") (pinfunction "2_2") (pintype "passive"))
    )
    (net (code "19") (name "/ILIM_EN") (class "Default")
      (node (ref "R19") (pin "2") (pinfunction "2_2") (pintype "passive"))
      (node (ref "U5") (pin "5") (pinfunction "PB1_5") (pintype "passive"))
    )
    (net (code "20") (name "/JD_DATA") (class "Default")
      (node (ref "D2") (pin "1") (pinfunction "K_1") (pintype "passive"))
      (node (ref "EC1") (pin "1") (pinfunction "D_1") (pintype "passive"))
      (node (ref "FB1") (pin "1") (pinfunction "1_1") (pintype "passive"))
      (node (ref "J6") (pin "2") (pinfunction "1_2") (pintype "passive"))
      (node (ref "MH1") (pin "1") (pinfunction "1_1") (pintype "passive"))
    )
    (net (code "21") (name "/JD_DATA_MCU{slash}ICPDA") (class "Default")
      (node (ref "D1") (pin "3") (pinfunction "A_3") (pintype "passive"))
      (node (ref "J2") (pin "2") (pinfunction "SWDIO_2") (pintype "passive"))
      (node (ref "R1") (pin "2") (pinfunction "2_2") (pintype "passive"))
      (node (ref "U3") (pin "12") (pinfunction "GPIO9_12") (pintype "passive"))
      (node (ref "U5") (pin "2") (pinfunction "PA6_2") (pintype "passive"))
    )
    (net (code "22") (name "/JD_RGB_B") (class "Default")
      (node (ref "R11") (pin "2") (pinfunction "2_2") (pintype "passive"))
      (node (ref "U3") (pin "18") (pinfunction "GPIO15_18") (pintype "passive"))
    )
    (net (code "23") (name "/JD_RGB_G") (class "Default")
      (node (ref "R12") (pin "2") (pinfunction "2_2") (pintype "passive"))
      (node (ref "U3") (pin "17") (pinfunction "GPIO14_17") (pintype "passive"))
    )
    (net (code "24") (name "/JD_RGB_R") (class "Default")
      (node (ref "R13") (pin "2") (pinfunction "2_2") (pintype "passive"))
      (node (ref "U3") (pin "27") (pinfunction "GPIO16_27") (pintype "passive"))
    )
    (net (code "25") (name "/JD_STATUS{slash}ICVPP") (class "Default")
      (node (ref "J2") (pin "5") (pinfunction "RESET_5") (pintype "passive"))
      (node (ref "U5") (pin "3") (pinfunction "PA5_3") (pintype "passive"))
    )
    (net (code "26") (name "/MCU_QSPI_SCLK") (class "Default")
      (node (ref "U3") (pin "52") (pinfunction "QSPI_SCLK_52") (pintype "passive"))
      (node (ref "U4") (pin "6") (pinfunction "CLK_6") (pintype "passive"))
    )
    (net (code "27") (name "/MCU_QSPI_SD0") (class "Default")
      (node (ref "U3") (pin "53") (pinfunction "QSPI_SD0_53") (pintype "passive"))
      (node (ref "U4") (pin "5") (pinfunction "DI(IO0)_5") (pintype "passive"))
    )
    (net (code "28") (name "/MCU_QSPI_SD1") (class "Default")
      (node (ref "U3") (pin "55") (pinfunction "QSPI_SD1_55") (pintype "passive"))
      (node (ref "U4") (pin "2") (pinfunction "DO(IO1)_2") (pintype "passive"))
    )
    (net (code "29") (name "/MCU_QSPI_SD2") (class "Default")
      (node (ref "U3") (pin "54") (pinfunction "QSPI_SD2_54") (pintype "passive"))
      (node (ref "U4") (pin "3") (pinfunction "~{WP}(IO2)_3") (pintype "passive"))
    )
    (net (code "30") (name "/MCU_QSPI_SD3") (class "Default")
      (node (ref "U3") (pin "51") (pinfunction "QSPI_SD3_51") (pintype "passive"))
      (node (ref "U4") (pin "7") (pinfunction "~{HOLD/RESET}(IO3)_7") (pintype "passive"))
    )
    (net (code "31") (name "/MCU_QSPI_SS") (class "Default")
      (node (ref "R7") (pin "2") (pinfunction "2_2") (pintype "passive"))
      (node (ref "R8") (pin "1") (pinfunction "1_1") (pintype "passive"))
      (node (ref "U3") (pin "56") (pinfunction "QSPI_SS_56") (pintype "passive"))
      (node (ref "U4") (pin "1") (pinfunction "~{CS}_1") (pintype "passive"))
    )
    (net (code "32") (name "/MCU_USB_D_N") (class "Default")
      (node (ref "R4") (pin "1") (pinfunction "1_1") (pintype "passive"))
      (node (ref "U3") (pin "46") (pinfunction "USB_DM_46") (pintype "passive"))
    )
    (net (code "33") (name "/MCU_USB_D_P") (class "Default")
      (node (ref "R3") (pin "1") (pinfunction "1_1") (pintype "passive"))
      (node (ref "U3") (pin "47") (pinfunction "USB_DP_47") (pintype "passive"))
    )
    (net (code "34") (name "/PD_STATUS") (class "Default")
      (node (ref "R16") (pin "1") (pinfunction "1_1") (pintype "passive"))
      (node (ref "U5") (pin "4") (pinfunction "PB7_4") (pintype "passive"))
    )
    (net (code "35") (name "/SWCLK") (class "Default")
      (node (ref "J1") (pin "4") (pinfunction "SWCLK_4") (pintype "passive"))
      (node (ref "U3") (pin "24") (pinfunction "SWCLK_24") (pintype "passive"))
    )
    (net (code "36") (name "/SWDIO") (class "Default")
      (node (ref "J1") (pin "2") (pinfunction "SWDIO_2") (pintype "passive"))
      (node (ref "U3") (pin "25") (pinfunction "SWD_25") (pintype "passive"))
    )
    (net (code "37") (name "/USB_D_N") (class "Default")
      (node (ref "D5") (pin "1") (pinfunction "K_1") (pintype "passive"))
      (node (ref "J3") (pin "A7") (pinfunction "D-_A7") (pintype "passive"))
      (node (ref "J3") (pin "B7") (pinfunction "D-_B7") (pintype "passive"))
      (node (ref "J5") (pin "19") (pinfunction "19_19") (pintype "passive"))
      (node (ref "R4") (pin "2") (pinfunction "2_2") (pintype "passive"))
    )
    (net (code "38") (name "/USB_D_P") (class "Default")
      (node (ref "D4") (pin "1") (pinfunction "K_1") (pintype "passive"))
      (node (ref "J3") (pin "A6") (pinfunction "D+_A6") (pintype "passive"))
      (node (ref "J3") (pin "B6") (pinfunction "D+_B6") (pintype "passive"))
      (node (ref "J5") (pin "17") (pinfunction "17_17") (pintype "passive"))
      (node (ref "R3") (pin "2") (pinfunction "2_2") (pintype "passive"))
    )
    (net (code "39") (name "/USB_WAKEUP{slash}ICPCK") (class "Default")
      (node (ref "J2") (pin "4") (pinfunction "SWCLK_4") (pintype "passive"))
      (node (ref "Q2") (pin "1") (pinfunction "G_1") (pintype "passive"))
      (node (ref "U5") (pin "6") (pinfunction "PA3_6") (pintype "passive"))
    )
    (net (code "40") (name "/VUSB_DET") (class "Default")
      (node (ref "C23") (pin "2") (pinfunction "2_2") (pintype "passive"))
      (node (ref "R21") (pin "1") (pinfunction "1_1") (pintype "passive"))
      (node (ref "R23") (pin "2") (pinfunction "2_2") (pintype "passive"))
    )
    (net (code "41") (name "/XIN") (class "Default")
      (node (ref "C20") (pin "1") (pinfunction "1_1") (pintype "passive"))
      (node (ref "U3") (pin "20") (pinfunction "XIN_20") (pintype "passive"))
      (node (ref "X1") (pin "3") (pinfunction "3_3") (pintype "passive"))
    )
    (net (code "42") (name "/XOUT") (class "Default")
      (node (ref "R9") (pin "2") (pinfunction "2_2") (pintype "passive"))
      (node (ref "U3") (pin "21") (pinfunction "XOUT_21") (pintype "passive"))
    )
    (net (code "43") (name "/~{BOOT}") (class "Default")
      (node (ref "Q1") (pin "2") (pinfunction "E_2") (pintype "passive"))
      (node (ref "R8") (pin "2") (pinfunction "2_2") (pintype "passive"))
    )
    (net (code "44") (name "/~{ILIM_HI}") (class "Default")
      (node (ref "R5") (pin "1") (pinfunction "1_1") (pintype "passive"))
    )
    (net (code "45") (name "/~{RESET}") (class "Default")
      (node (ref "J1") (pin "5") (pinfunction "RESET_5") (pintype "passive"))
      (node (ref "J5") (pin "3") (pinfunction "5_3") (pintype "passive"))
      (node (ref "R24") (pin "1") (pinfunction "1_1") (pintype "passive"))
      (node (ref "SW1") (pin "1") (pinfunction "1_1") (pintype "passive"))
      (node (ref "SW1") (pin "2") (pinfunction "2_2") (pintype "passive"))
      (node (ref "U3") (pin "26") (pinfunction "RUN_26") (pintype "passive"))
    )
    (net (code "46") (name "1V1") (class "Default")
      (node (ref "C13") (pin "2") (pinfunction "2_2") (pintype "passive"))
      (node (ref "C14") (pin "2") (pinfunction "2_2") (pintype "passive"))
      (node (ref "C15") (pin "2") (pinfunction "2_2") (pintype "passive"))
      (node (ref "U3") (pin "23") (pinfunction "DVDD_23") (pintype "passive"))
      (node (ref "U3") (pin "45") (pinfunction "VREG_VOUT_45") (pintype "passive"))
      (node (ref "U3") (pin "50") (pinfunction "DVDD_50") (pintype "passive"))
    )
    (net (code "47") (name "3V3") (class "Default")
      (node (ref "C10") (pin "2") (pinfunction "2_2") (pintype "passive"))
      (node (ref "C11") (pin "2") (pinfunction "2_2") (pintype "passive"))
      (node (ref "C12") (pin "2") (pinfunction "2_2") (pintype "passive"))
      (node (ref "C16") (pin "2") (pinfunction "2_2") (pintype "passive"))
      (node (ref "C19") (pin "2") (pinfunction "2_2") (pintype "passive"))
      (node (ref "C3") (pin "2") (pinfunction "2_2") (pintype "passive"))
      (node (ref "C7") (pin "2") (pinfunction "2_2") (pintype "passive"))
      (node (ref "C8") (pin "2") (pinfunction "2_2") (pintype "passive"))
      (node (ref "C9") (pin "2") (pinfunction "2_2") (pintype "passive"))
      (node (ref "D1") (pin "2") (pinfunction "K_2") (pintype "passive"))
      (node (ref "D9") (pin "1") (pinfunction "A_1") (pintype "passive"))
      (node (ref "J1") (pin "1") (pinfunction "VCC_1") (pintype "passive"))
      (node (ref "J2") (pin "1") (pinfunction "VCC_1") (pintype "passive"))
      (node (ref "R2") (pin "1") (pinfunction "1_1") (pintype "passive"))
      (node (ref "R7") (pin "1") (pinfunction "1_1") (pintype "passive"))
      (node (ref "U1") (pin "5") (pinfunction "OUT_5") (pintype "passive"))
      (node (ref "U3") (pin "1") (pinfunction "IOVDD_1") (pintype "passive"))
      (node (ref "U3") (pin "10") (pinfunction "IOVDD_10") (pintype "passive"))
      (node (ref "U3") (pin "22") (pinfunction "IOVDD_22") (pintype "passive"))
      (node (ref "U3") (pin "33") (pinfunction "IOVDD_33") (pintype "passive"))
      (node (ref "U3") (pin "42") (pinfunction "IOVDD_42") (pintype "passive"))
      (node (ref "U3") (pin "43") (pinfunction "ADC_AVDD_43") (pintype "passive"))
      (node (ref "U3") (pin "44") (pinfunction "VREG_IN_44") (pintype "passive"))
      (node (ref "U3") (pin "48") (pinfunction "USB_VDD_48") (pintype "passive"))
      (node (ref "U3") (pin "49") (pinfunction "IOVDD_49") (pintype "passive"))
      (node (ref "U4") (pin "8") (pinfunction "VCC_8") (pintype "power_in"))
      (node (ref "U5") (pin "1") (pinfunction "VDD_1") (pintype "passive"))
    )
    (net (code "48") (name "GND") (class "Default")
      (node (ref "C1") (pin "1") (pinfunction "1_1") (pintype "passive"))
      (node (ref "C10") (pin "1") (pinfunction "1_1") (pintype "passive"))
      (node (ref "C11") (pin "1") (pinfunction "1_1") (pintype "passive"))
      (node (ref "C12") (pin "1") (pinfunction "1_1") (pintype "passive"))
      (node (ref "C13") (pin "1") (pinfunction "1_1") (pintype "passive"))
      (node (ref "C14") (pin "1") (pinfunction "1_1") (pintype "passive"))
      (node (ref "C15") (pin "1") (pinfunction "1_1") (pintype "passive"))
      (node (ref "C16") (pin "1") (pinfunction "1_1") (pintype "passive"))
      (node (ref "C19") (pin "1") (pinfunction "1_1") (pintype "passive"))
      (node (ref "C2") (pin "1") (pinfunction "1_1") (pintype "passive"))
      (node (ref "C20") (pin "2") (pinfunction "2_2") (pintype "passive"))
      (node (ref "C21") (pin "2") (pinfunction "2_2") (pintype "passive"))
      (node (ref "C22") (pin "1") (pinfunction "1_1") (pintype "passive"))
      (node (ref "C23") (pin "1") (pinfunction "1_1") (pintype "passive"))
      (node (ref "C24") (pin "1") (pinfunction "1_1") (pintype "passive"))
      (node (ref "C25") (pin "2") (pinfunction "2_2") (pintype "passive"))
      (node (ref "C26") (pin "2") (pinfunction "2_2") (pintype "passive"))
      (node (ref "C3") (pin "1") (pinfunction "1_1") (pintype "passive"))
      (node (ref "C4") (pin "1") (pinfunction "1_1") (pintype "passive"))
      (node (ref "C5") (pin "1") (pinfunction "1_1") (pintype "passive"))
      (node (ref "C6") (pin "1") (pinfunction "1_1") (pintype "passive"))
      (node (ref "C7") (pin "1") (pinfunction "1_1") (pintype "passive"))
      (node (ref "C8") (pin "1") (pinfunction "1_1") (pintype "passive"))
      (node (ref "C9") (pin "1") (pinfunction "1_1") (pintype "passive"))
      (node (ref "D1") (pin "1") (pinfunction "A_1") (pintype "passive"))
      (node (ref "D2") (pin "2") (pinfunction "A_2") (pintype "passive"))
      (node (ref "D3") (pin "2") (pinfunction "A_2") (pintype "passive"))
      (node (ref "D4") (pin "2") (pinfunction "A_2") (pintype "passive"))
      (node (ref "D5") (pin "2") (pinfunction "A_2") (pintype "passive"))
      (node (ref "D6") (pin "2") (pinfunction "A_2") (pintype "passive"))
      (node (ref "EC1") (pin "2") (pinfunction "G_2") (pintype "passive"))
      (node (ref "J1") (pin "3") (pinfunction "GND_3") (pintype "passive"))
      (node (ref "J2") (pin "3") (pinfunction "GND_3") (pintype "passive"))
      (node (ref "J3") (pin "A1") (pinfunction "GND_A1") (pintype "passive"))
      (node (ref "J3") (pin "A12") (pinfunction "GND_A12") (pintype "passive"))
      (node (ref "J3") (pin "B1") (pinfunction "GND_B1") (pintype "passive"))
      (node (ref "J3") (pin "B12") (pinfunction "GND_B12") (pintype "passive"))
      (node (ref "J5") (pin "23") (pinfunction "23_23") (pintype "passive"))
      (node (ref "J6") (pin "24") (pinfunction "23_24") (pintype "passive"))
      (node (ref "MH2") (pin "1") (pinfunction "1_1") (pintype "passive"))
      (node (ref "MH4") (pin "1") (pinfunction "1_1") (pintype "passive"))
      (node (ref "Q1") (pin "3") (pinfunction "C_3") (pintype "passive"))
      (node (ref "Q2") (pin "2") (pinfunction "S_2") (pintype "passive"))
      (node (ref "R14") (pin "2") (pinfunction "2_2") (pintype "passive"))
      (node (ref "R15") (pin "2") (pinfunction "2_2") (pintype "passive"))
      (node (ref "R17") (pin "2") (pinfunction "2_2") (pintype "passive"))
      (node (ref "R22") (pin "1") (pinfunction "1_1") (pintype "passive"))
      (node (ref "R23") (pin "1") (pinfunction "1_1") (pintype "passive"))
      (node (ref "R6") (pin "1") (pinfunction "1_1") (pintype "passive"))
      (node (ref "SW1") (pin "3") (pinfunction "3_3") (pintype "passive"))
      (node (ref "SW1") (pin "4") (pinfunction "4_4") (pintype "passive"))
      (node (ref "U1") (pin "2") (pinfunction "GND_2") (pintype "passive"))
      (node (ref "U2") (pin "2") (pinfunction "GND_2") (pintype "passive"))
      (node (ref "U3") (pin "19") (pinfunction "TESTEN_19") (pintype "passive"))
      (node (ref "U3") (pin "57") (pinfunction "EXP_57") (pintype "passive"))
      (node (ref "U4") (pin "4") (pinfunction "GND_4") (pintype "power_in"))
      (node (ref "U5") (pin "8") (pinfunction "GND_8") (pintype "passive"))
      (node (ref "X1") (pin "2") (pinfunction "2_2") (pintype "passive"))
      (node (ref "X1") (pin "4") (pinfunction "4_4") (pintype "passive"))
    )
    (net (code "49") (name "ILIM_OUT") (class "Default")
      (node (ref "C6") (pin "2") (pinfunction "2_2") (pintype "passive"))
      (node (ref "D10") (pin "2") (pinfunction "A_2") (pintype "passive"))
      (node (ref "D8") (pin "2") (pinfunction "A_2") (pintype "passive"))
      (node (ref "R20") (pin "2") (pinfunction "2_2") (pintype "passive"))
      (node (ref "U2") (pin "6") (pinfunction "OUT_6") (pintype "passive"))
    )
    (net (code "50") (name "JD_PWR") (class "Default")
      (node (ref "D10") (pin "1") (pinfunction "K_1") (pintype "passive"))
      (node (ref "D12") (pin "2") (pinfunction "A_2") (pintype "passive"))
      (node (ref "D3") (pin "1") (pinfunction "K_1") (pintype "passive"))
      (node (ref "EC1") (pin "3") (pinfunction "P_3") (pintype "passive"))
      (node (ref "J5") (pin "1") (pinfunction "1_1") (pintype "passive"))
      (node (ref "MH3") (pin "1") (pinfunction "1_1") (pintype "passive"))
    )
    (net (code "51") (name "Net-(C1-Pad2)") (class "Default")
      (node (ref "C1") (pin "2") (pinfunction "2_2") (pintype "passive"))
      (node (ref "FB1") (pin "2") (pinfunction "2_2") (pintype "passive"))
      (node (ref "R1") (pin "1") (pinfunction "1_1") (pintype "passive"))
    )
    (net (code "52") (name "Net-(C21-Pad1)") (class "Default")
      (node (ref "C21") (pin "1") (pinfunction "1_1") (pintype "passive"))
      (node (ref "R9") (pin "1") (pinfunction "1_1") (pintype "passive"))
      (node (ref "X1") (pin "1") (pinfunction "1_1") (pintype "passive"))
    )
    (net (code "53") (name "Net-(D8-K)") (class "Default")
      (node (ref "D8") (pin "1") (pinfunction "K_1") (pintype "passive"))
      (node (ref "R16") (pin "2") (pinfunction "2_2") (pintype "passive"))
      (node (ref "R17") (pin "1") (pinfunction "1_1") (pintype "passive"))
    )
    (net (code "54") (name "Net-(D9-B)") (class "Default")
      (node (ref "D9") (pin "4") (pinfunction "B_4") (pintype "passive"))
      (node (ref "R11") (pin "1") (pinfunction "1_1") (pintype "passive"))
    )
    (net (code "55") (name "Net-(D9-G)") (class "Default")
      (node (ref "D9") (pin "3") (pinfunction "G_3") (pintype "passive"))
      (node (ref "R12") (pin "1") (pinfunction "1_1") (pintype "passive"))
    )
    (net (code "56") (name "Net-(D9-R)") (class "Default")
      (node (ref "D9") (pin "2") (pinfunction "R_2") (pintype "passive"))
      (node (ref "R13") (pin "1") (pinfunction "1_1") (pintype "passive"))
    )
    (net (code "57") (name "Net-(D11-K)") (class "Default")
      (node (ref "C2") (pin "2") (pinfunction "2_2") (pintype "passive"))
      (node (ref "D11") (pin "1") (pinfunction "K_1") (pintype "passive"))
      (node (ref "D12") (pin "1") (pinfunction "K_1") (pintype "passive"))
      (node (ref "U1") (pin "1") (pinfunction "IN_1") (pintype "passive"))
      (node (ref "U1") (pin "3") (pinfunction "EN_3") (pintype "passive"))
    )
    (net (code "58") (name "Net-(Q1-B)") (class "Default")
      (node (ref "C24") (pin "2") (pinfunction "2_2") (pintype "passive"))
      (node (ref "Q1") (pin "1") (pinfunction "B_1") (pintype "passive"))
      (node (ref "R24") (pin "2") (pinfunction "2_2") (pintype "passive"))
    )
    (net (code "59") (name "Net-(Q2-D)") (class "Default")
      (node (ref "Q2") (pin "3") (pinfunction "D_3") (pintype "passive"))
      (node (ref "R18") (pin "1") (pinfunction "1_1") (pintype "passive"))
    )
    (net (code "60") (name "Net-(U2-EN)") (class "Default")
      (node (ref "C5") (pin "2") (pinfunction "2_2") (pintype "passive"))
      (node (ref "R19") (pin "1") (pinfunction "1_1") (pintype "passive"))
      (node (ref "R2") (pin "2") (pinfunction "2_2") (pintype "passive"))
      (node (ref "U2") (pin "3") (pinfunction "EN_3") (pintype "passive"))
      (node (ref "U2") (pin "4") (pinfunction "~{FAULT}_4") (pintype "passive"))
    )
    (net (code "61") (name "Net-(U2-ILIM)") (class "Default")
      (node (ref "R5") (pin "2") (pinfunction "2_2") (pintype "passive"))
      (node (ref "R6") (pin "2") (pinfunction "2_2") (pintype "passive"))
      (node (ref "SB1") (pin "1") (pinfunction "1_1") (pintype "passive"))
      (node (ref "U2") (pin "5") (pinfunction "ILIM_5") (pintype "passive"))
    )
    (net (code "62") (name "Net-(U3-GPIO2)") (class "Default")
      (node (ref "R25") (pin "1") (pinfunction "1_1") (pintype "passive"))
      (node (ref "U3") (pin "4") (pinfunction "GPIO2_4") (pintype "passive"))
    )
    (net (code "63") (name "Net-(U3-GPIO3)") (class "Default")
      (node (ref "R26") (pin "1") (pinfunction "1_1") (pintype "passive"))
      (node (ref "U3") (pin "5") (pinfunction "GPIO3_5") (pintype "passive"))
    )
    (net (code "64") (name "VUSB") (class "Default")
      (node (ref "C4") (pin "2") (pinfunction "2_2") (pintype "passive"))
      (node (ref "D11") (pin "2") (pinfunction "A_2") (pintype "passive"))
      (node (ref "D6") (pin "1") (pinfunction "K_1") (pintype "passive"))
      (node (ref "J3") (pin "A4") (pinfunction "VBUS_A4") (pintype "passive"))
      (node (ref "J3") (pin "A9") (pinfunction "VBUS_A9") (pintype "passive"))
      (node (ref "J3") (pin "B4") (pinfunction "VBUS_B4") (pintype "passive"))
      (node (ref "J3") (pin "B9") (pinfunction "VBUS_B9") (pintype "passive"))
      (node (ref "J5") (pin "21") (pinfunction "21_21") (pintype "passive"))
      (node (ref "R18") (pin "2") (pinfunction "2_2") (pintype "passive"))
      (node (ref "R21") (pin "2") (pinfunction "2_2") (pintype "passive"))
      (node (ref "SB1") (pin "2") (pinfunction "2_2") (pintype "passive"))
      (node (ref "U2") (pin "1") (pinfunction "IN_1") (pintype "passive"))
    )
    (net (code "65") (name "unconnected-(J3-SBU1-PadA8)") (class "Default")
      (node (ref "J3") (pin "A8") (pinfunction "SBU1_A8") (pintype "passive+no_connect"))
    )
    (net (code "66") (name "unconnected-(J3-SBU2-PadB8)") (class "Default")
      (node (ref "J3") (pin "B8") (pinfunction "SBU2_B8") (pintype "passive+no_connect"))
    )
    (net (code "67") (name "unconnected-(U3-GPIO8-Pad11)") (class "Default")
      (node (ref "U3") (pin "11") (pinfunction "GPIO8_11") (pintype "passive+no_connect"))
    )
    (net (code "68") (name "unconnected-(U3-GPIO11-Pad14)") (class "Default")
      (node (ref "U3") (pin "14") (pinfunction "GPIO11_14") (pintype "passive+no_connect"))
    )
    (net (code "69") (name "unconnected-(U3-GPIO12-Pad15)") (class "Default")
      (node (ref "U3") (pin "15") (pinfunction "GPIO12_15") (pintype "passive+no_connect"))
    )
    (net (code "70") (name "unconnected-(U3-GPIO13-Pad16)") (class "Default")
      (node (ref "U3") (pin "16") (pinfunction "GPIO13_16") (pintype "passive+no_connect"))
    )
    (net (code "71") (name "unconnected-(U3-GPIO17-Pad28)") (class "Default")
      (node (ref "U3") (pin "28") (pinfunction "GPIO17_28") (pintype "passive+no_connect"))
    )
    (net (code "72") (name "unconnected-(U3-GPIO18-Pad29)") (class "Default")
      (node (ref "U3") (pin "29") (pinfunction "GPIO18_29") (pintype "passive+no_connect"))
    )
    (net (code "73") (name "unconnected-(U3-GPIO19-Pad30)") (class "Default")
      (node (ref "U3") (pin "30") (pinfunction "GPIO19_30") (pintype "passive+no_connect"))
    )
    (net (code "74") (name "unconnected-(U3-GPIO20-Pad31)") (class "Default")
      (node (ref "U3") (pin "31") (pinfunction "GPIO20_31") (pintype "passive+no_connect"))
    )
    (net (code "75") (name "unconnected-(U3-GPIO21-Pad32)") (class "Default")
      (node (ref "U3") (pin "32") (pinfunction "GPIO21_32") (pintype "passive+no_connect"))
    )
    (net (code "76") (name "unconnected-(U3-GPIO22-Pad34)") (class "Default")
      (node (ref "U3") (pin "34") (pinfunction "GPIO22_34") (pintype "passive+no_connect"))
    )
    (net (code "77") (name "unconnected-(U3-GPIO23-Pad35)") (class "Default")
      (node (ref "U3") (pin "35") (pinfunction "GPIO23_35") (pintype "passive+no_connect"))
    )
    (net (code "78") (name "unconnected-(U5-PA4-Pad7)") (class "Default")
      (node (ref "U5") (pin "7") (pinfunction "PA4_7") (pintype "passive"))
    )
  )
)
